# Color_sensor_LED_Board.net
KiCad netlist of a schematic drawn in EAGLE
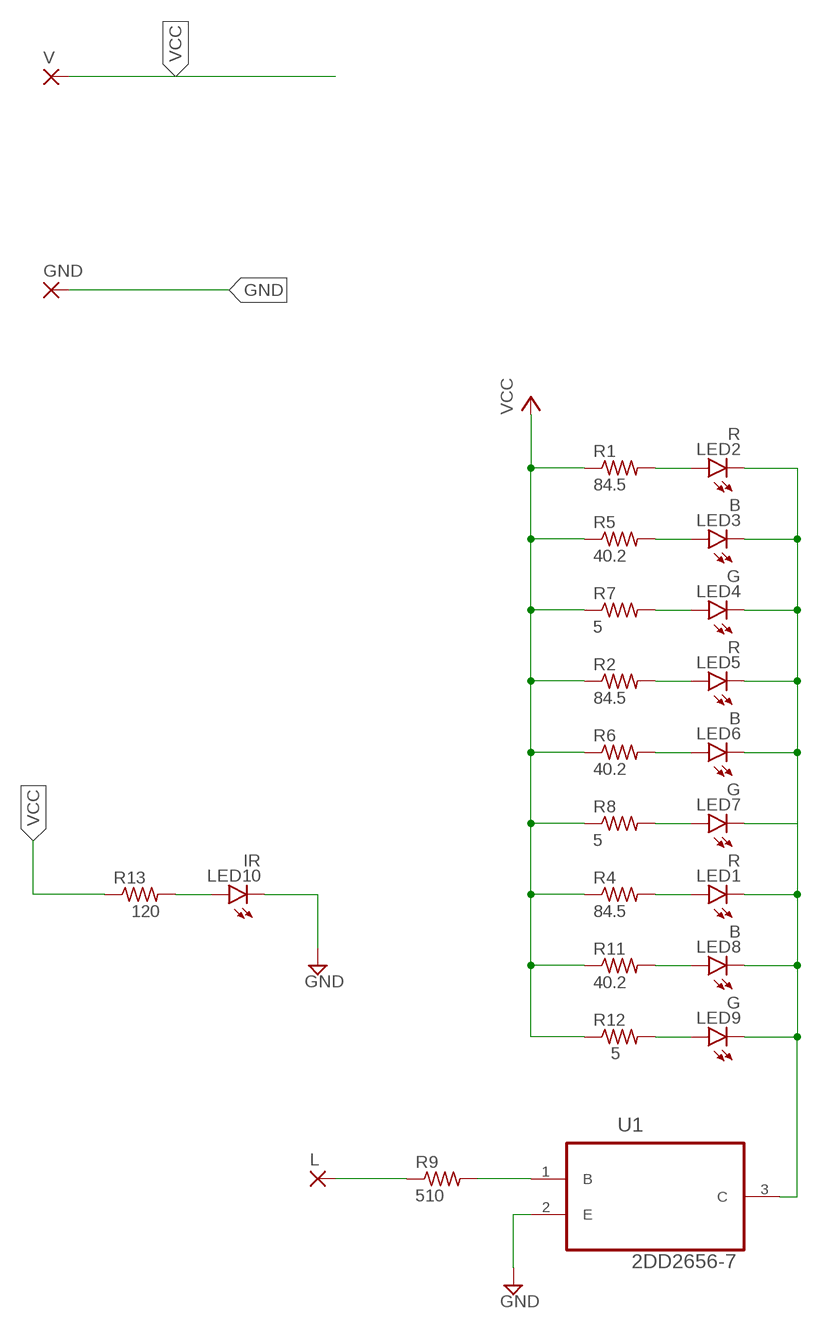
[diagram p0: schematic, sheet 1]

(export (version "E")
  (design (tool "Eeschema 10.0.6"))
  (components
    (comp (ref "GND")
      (value "SMD2")
      (footprint "eagle-import:SMD1,27-2,54")
      (libsource (lib "eagle-import") (part "SMD2"))
    )
    (comp (ref "L")
      (value "SMD2")
      (footprint "eagle-import:SMD1,27-2,54")
      (libsource (lib "eagle-import") (part "SMD2"))
    )
    (comp (ref "LED1")
      (value "R")
      (footprint "eagle-import:CHIPLED_0805")
      (libsource (lib "eagle-import") (part "LEDCHIPLED_0805"))
    )
    (comp (ref "LED2")
      (value "R")
      (footprint "eagle-import:CHIPLED_0805")
      (libsource (lib "eagle-import") (part "LEDCHIPLED_0805"))
    )
    (comp (ref "LED3")
      (value "B")
      (footprint "eagle-import:CHIPLED_0805")
      (libsource (lib "eagle-import") (part "LEDCHIPLED_0805"))
    )
    (comp (ref "LED4")
      (value "G")
      (footprint "eagle-import:CHIPLED_0805")
      (libsource (lib "eagle-import") (part "LEDCHIPLED_0805"))
    )
    (comp (ref "LED5")
      (value "R")
      (footprint "eagle-import:CHIPLED_0805")
      (libsource (lib "eagle-import") (part "LEDCHIPLED_0805"))
    )
    (comp (ref "LED6")
      (value "B")
      (footprint "eagle-import:CHIPLED_0805")
      (libsource (lib "eagle-import") (part "LEDCHIPLED_0805"))
    )
    (comp (ref "LED7")
      (value "G")
      (footprint "eagle-import:CHIPLED_0805")
      (libsource (lib "eagle-import") (part "LEDCHIPLED_0805"))
    )
    (comp (ref "LED8")
      (value "B")
      (footprint "eagle-import:CHIPLED_0805")
      (libsource (lib "eagle-import") (part "LEDCHIPLED_0805"))
    )
    (comp (ref "LED9")
      (value "G")
      (footprint "eagle-import:CHIPLED_0805")
      (libsource (lib "eagle-import") (part "LEDCHIPLED_0805"))
    )
    (comp (ref "LED10")
      (value "IR")
      (footprint "eagle-import:CHIPLED_0805")
      (libsource (lib "eagle-import") (part "LEDCHIPLED_0805"))
    )
    (comp (ref "R1")
      (value "84.5")
      (footprint "eagle-import:R0805")
      (libsource (lib "eagle-import") (part "R-US_R0805"))
    )
    (comp (ref "R2")
      (value "84.5")
      (footprint "eagle-import:R0805")
      (libsource (lib "eagle-import") (part "R-US_R0805"))
    )
    (comp (ref "R4")
      (value "84.5")
      (footprint "eagle-import:R0805")
      (libsource (lib "eagle-import") (part "R-US_R0805"))
    )
    (comp (ref "R5")
      (value "40.2")
      (footprint "eagle-import:R0805")
      (libsource (lib "eagle-import") (part "R-US_R0805"))
    )
    (comp (ref "R6")
      (value "40.2")
      (footprint "eagle-import:R0805")
      (libsource (lib "eagle-import") (part "R-US_R0805"))
    )
    (comp (ref "R7")
      (value "5")
      (footprint "eagle-import:R0805")
      (libsource (lib "eagle-import") (part "R-US_R0805"))
    )
    (comp (ref "R8")
      (value "5")
      (footprint "eagle-import:R0805")
      (libsource (lib "eagle-import") (part "R-US_R0805"))
    )
    (comp (ref "R9")
      (value "510")
      (footprint "eagle-import:R0805")
      (libsource (lib "eagle-import") (part "R-US_R0805"))
    )
    (comp (ref "R11")
      (value "40.2")
      (footprint "eagle-import:R0805")
      (libsource (lib "eagle-import") (part "R-US_R0805"))
    )
    (comp (ref "R12")
      (value "5")
      (footprint "eagle-import:R0805")
      (libsource (lib "eagle-import") (part "R-US_R0805"))
    )
    (comp (ref "R13")
      (value "120")
      (footprint "eagle-import:R0805")
      (libsource (lib "eagle-import") (part "R-US_R0805"))
    )
    (comp (ref "U1")
      (value "2DD2656-7")
      (footprint "eagle-import:SOT65P210X110-3N")
      (fields (field (name "MF") "Diodes Zetex"))
      (libsource (lib "eagle-import") (part "2DD2656-7"))
    )
    (comp (ref "V")
      (value "SMD2")
      (footprint "eagle-import:SMD1,27-2,54")
      (libsource (lib "eagle-import") (part "SMD2"))
    )
  )
  (nets
    (net (code "1") (name "GND") (class "Default")
      (node (ref "GND") (pin "1") (pinfunction "P_1") (pintype "passive"))
      (node (ref "LED10") (pin "C") (pinfunction "C_C") (pintype "passive"))
      (node (ref "U1") (pin "2") (pinfunction "E_2") (pintype "input"))
    )
    (net (code "2") (name "Net-(L-P)") (class "Default")
      (node (ref "L") (pin "1") (pinfunction "P_1") (pintype "passive"))
      (node (ref "R9") (pin "1") (pinfunction "1_1") (pintype "passive"))
    )
    (net (code "3") (name "Net-(LED1-PadA)") (class "Default")
      (node (ref "LED1") (pin "A") (pinfunction "A_A") (pintype "passive"))
      (node (ref "R4") (pin "2") (pinfunction "2_2") (pintype "passive"))
    )
    (net (code "4") (name "Net-(LED2-PadA)") (class "Default")
      (node (ref "LED2") (pin "A") (pinfunction "A_A") (pintype "passive"))
      (node (ref "R1") (pin "2") (pinfunction "2_2") (pintype "passive"))
    )
    (net (code "5") (name "Net-(LED3-PadA)") (class "Default")
      (node (ref "LED3") (pin "A") (pinfunction "A_A") (pintype "passive"))
      (node (ref "R5") (pin "2") (pinfunction "2_2") (pintype "passive"))
    )
    (net (code "6") (name "Net-(LED4-PadA)") (class "Default")
      (node (ref "LED4") (pin "A") (pinfunction "A_A") (pintype "passive"))
      (node (ref "R7") (pin "2") (pinfunction "2_2") (pintype "passive"))
    )
    (net (code "7") (name "Net-(LED5-PadA)") (class "Default")
      (node (ref "LED5") (pin "A") (pinfunction "A_A") (pintype "passive"))
      (node (ref "R2") (pin "2") (pinfunction "2_2") (pintype "passive"))
    )
    (net (code "8") (name "Net-(LED6-PadA)") (class "Default")
      (node (ref "LED6") (pin "A") (pinfunction "A_A") (pintype "passive"))
      (node (ref "R6") (pin "2") (pinfunction "2_2") (pintype "passive"))
    )
    (net (code "9") (name "Net-(LED7-PadA)") (class "Default")
      (node (ref "LED7") (pin "A") (pinfunction "A_A") (pintype "passive"))
      (node (ref "R8") (pin "2") (pinfunction "2_2") (pintype "passive"))
    )
    (net (code "10") (name "Net-(LED8-PadA)") (class "Default")
      (node (ref "LED8") (pin "A") (pinfunction "A_A") (pintype "passive"))
      (node (ref "R11") (pin "2") (pinfunction "2_2") (pintype "passive"))
    )
    (net (code "11") (name "Net-(LED9-PadA)") (class "Default")
      (node (ref "LED9") (pin "A") (pinfunction "A_A") (pintype "passive"))
      (node (ref "R12") (pin "2") (pinfunction "2_2") (pintype "passive"))
    )
    (net (code "12") (name "Net-(LED10-PadA)") (class "Default")
      (node (ref "LED10") (pin "A") (pinfunction "A_A") (pintype "passive"))
      (node (ref "R13") (pin "2") (pinfunction "2_2") (pintype "passive"))
    )
    (net (code "13") (name "Net-(U1-B)") (class "Default")
      (node (ref "R9") (pin "2") (pinfunction "2_2") (pintype "passive"))
      (node (ref "U1") (pin "1") (pinfunction "B_1") (pintype "input"))
    )
    (net (code "14") (name "Net-(U1-C)") (class "Default")
      (node (ref "LED1") (pin "C") (pinfunction "C_C") (pintype "passive"))
      (node (ref "LED2") (pin "C") (pinfunction "C_C") (pintype "passive"))
      (node (ref "LED3") (pin "C") (pinfunction "C_C") (pintype "passive"))
      (node (ref "LED4") (pin "C") (pinfunction "C_C") (pintype "passive"))
      (node (ref "LED5") (pin "C") (pinfunction "C_C") (pintype "passive"))
      (node (ref "LED6") (pin "C") (pinfunction "C_C") (pintype "passive"))
      (node (ref "LED7") (pin "C") (pinfunction "C_C") (pintype "passive"))
      (node (ref "LED8") (pin "C") (pinfunction "C_C") (pintype "passive"))
      (node (ref "LED9") (pin "C") (pinfunction "C_C") (pintype "passive"))
      (node (ref "U1") (pin "3") (pinfunction "C_3") (pintype "output"))
    )
    (net (code "15") (name "VCC") (class "Default")
      (node (ref "R1") (pin "1") (pinfunction "1_1") (pintype "passive"))
      (node (ref "R11") (pin "1") (pinfunction "1_1") (pintype "passive"))
      (node (ref "R12") (pin "1") (pinfunction "1_1") (pintype "passive"))
      (node (ref "R13") (pin "1") (pinfunction "1_1") (pintype "passive"))
      (node (ref "R2") (pin "1") (pinfunction "1_1") (pintype "passive"))
      (node (ref "R4") (pin "1") (pinfunction "1_1") (pintype "passive"))
      (node (ref "R5") (pin "1") (pinfunction "1_1") (pintype "passive"))
      (node (ref "R6") (pin "1") (pinfunction "1_1") (pintype "passive"))
      (node (ref "R7") (pin "1") (pinfunction "1_1") (pintype "passive"))
      (node (ref "R8") (pin "1") (pinfunction "1_1") (pintype "passive"))
      (node (ref "V") (pin "1") (pinfunction "P_1") (pintype "passive"))
    )
  )
)
